# Contact_V1_0.net
KiCad netlist of a schematic drawn in EAGLE
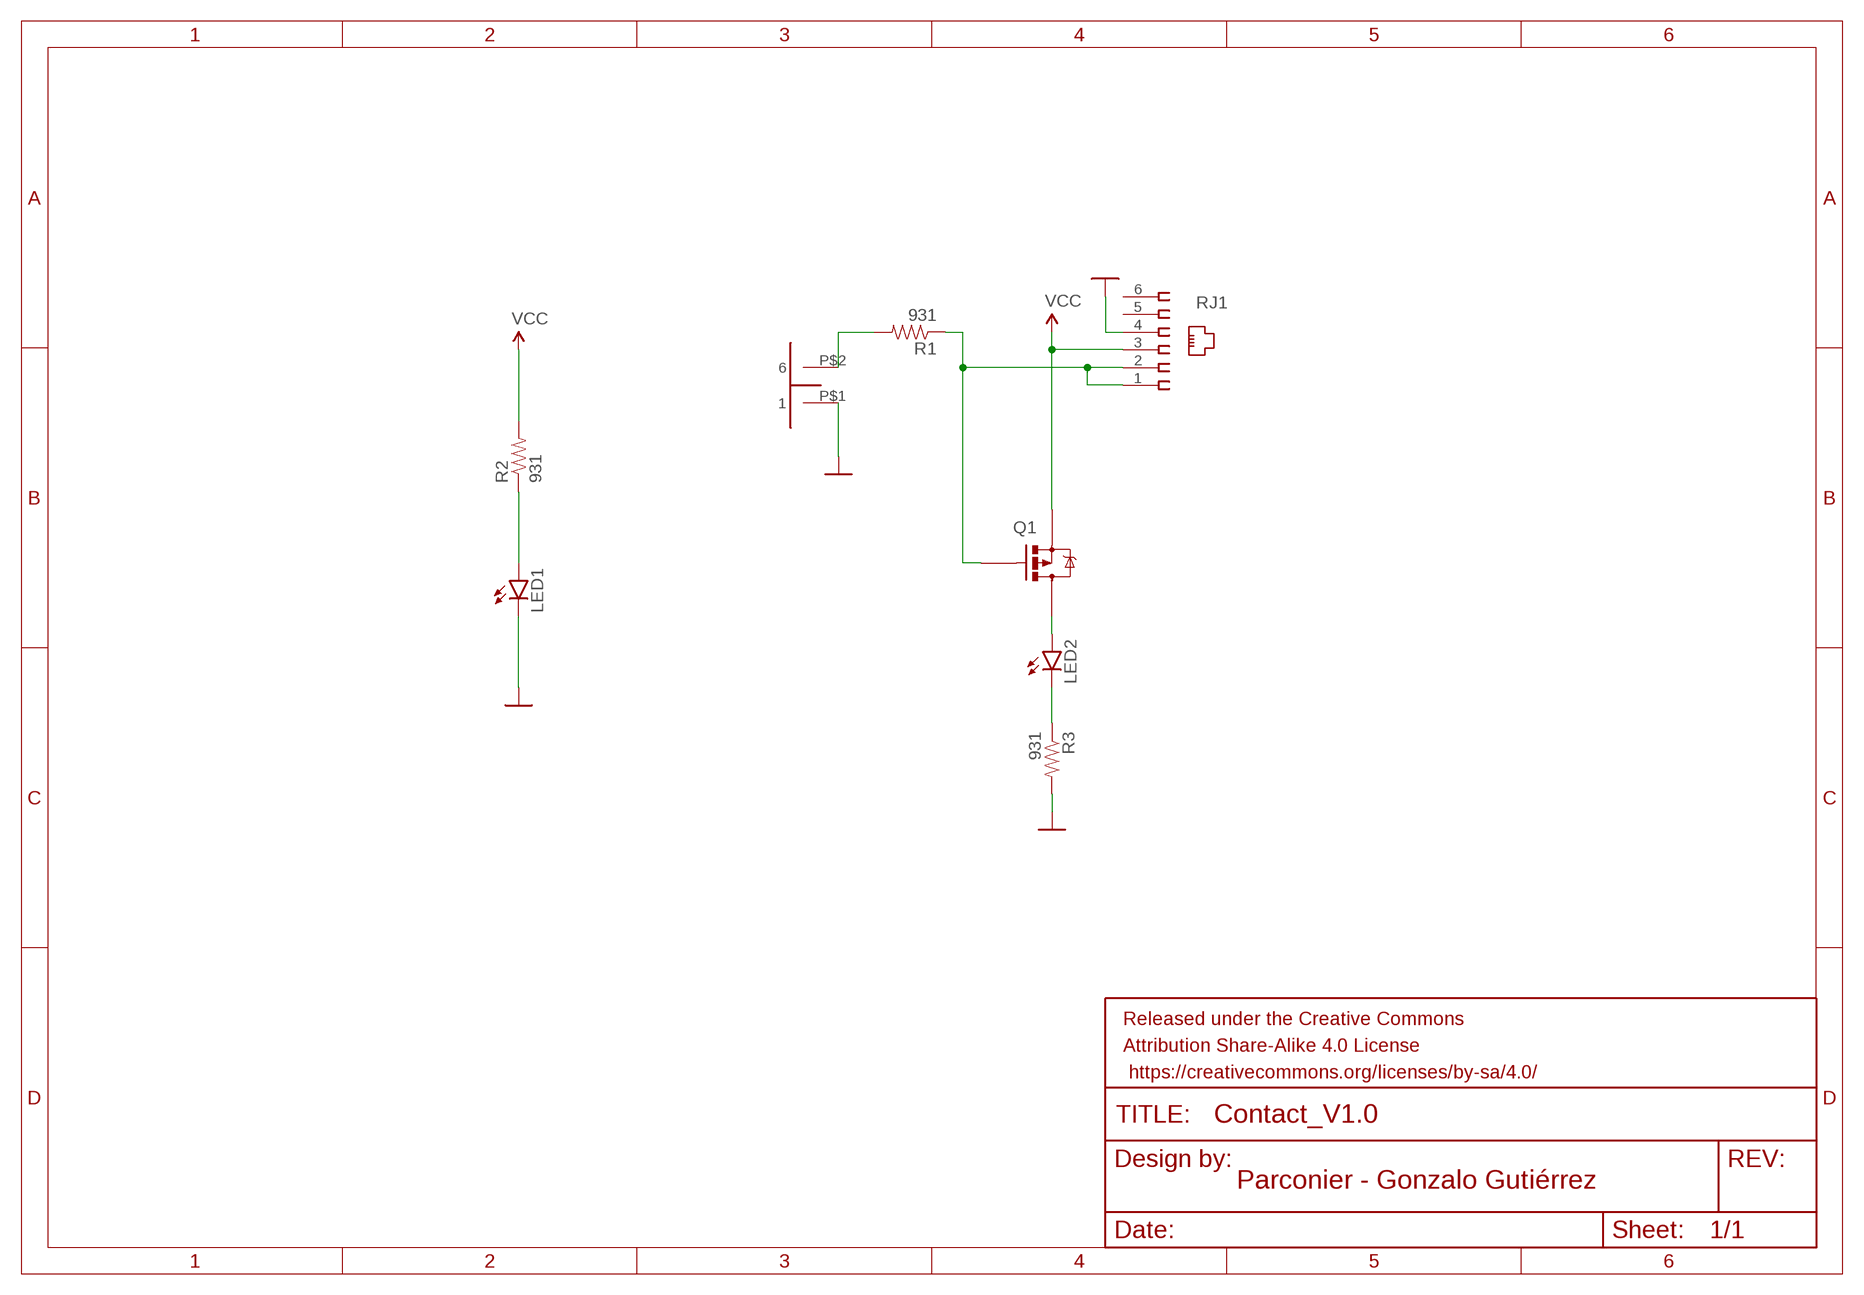
[diagram p0: schematic, sheet 1]

(export (version "E")
  (design (tool "Eeschema 10.0.6"))
  (components
    (comp (ref "LED1")
      (value "LED0603")
      (footprint "eagle-import:LED-0603")
      (fields (field (name "MPN") "LTST-C193KRKT-5A"))
      (libsource (lib "eagle-import") (part "LED0603"))
    )
    (comp (ref "LED2")
      (value "LED0603")
      (footprint "eagle-import:LED-0603")
      (fields (field (name "MPN") "LB Q39E-L2OO-35-1"))
      (libsource (lib "eagle-import") (part "LED0603"))
    )
    (comp (ref "PB1")
      (value "PUSHBUTTON_MOKO")
      (footprint "eagle-import:SUBSTITUTE_FSM104_RIGHT_ANGLE")
      (libsource (lib "eagle-import") (part "PUSHBUTTON_MOKO"))
    )
    (comp (ref "Q1")
      (value "RU1C002ZPTCL")
      (footprint "eagle-import:SOTFL65P210X105-3N")
      (libsource (lib "eagle-import") (part "RU1C002ZPTCL"))
    )
    (comp (ref "R1")
      (value "931")
      (footprint "eagle-import:RESC1005X35")
      (fields (field (name "MPN") "RC0402FR-07931RL"))
      (libsource (lib "eagle-import") (part "RES_0402"))
    )
    (comp (ref "R2")
      (value "931")
      (footprint "eagle-import:RESC1005X35")
      (fields (field (name "MPN") "RC0402FR-07931RL"))
      (libsource (lib "eagle-import") (part "RES_0402"))
    )
    (comp (ref "R3")
      (value "931")
      (footprint "eagle-import:RESC1005X35")
      (fields (field (name "MPN") "RC0402FR-07931RL"))
      (libsource (lib "eagle-import") (part "RES_0402"))
    )
    (comp (ref "RJ1")
      (value "615006138421")
      (footprint "eagle-import:615006138421")
      (fields (field (name "RS_PART_NUMBER") "7350282"))
      (libsource (lib "eagle-import") (part "615006138421"))
    )
  )
  (nets
    (net (code "1") (name "GND") (class "Default")
      (node (ref "LED1") (pin "C") (pinfunction "C_C") (pintype "passive"))
      (node (ref "PB1") (pin "P$1") (pinfunction "1_P$1") (pintype "bidirectional"))
      (node (ref "R3") (pin "2") (pinfunction "2_2") (pintype "passive"))
      (node (ref "RJ1") (pin "4") (pinfunction "4_4") (pintype "input"))
    )
    (net (code "2") (name "Net-(LED1-PadA)") (class "Default")
      (node (ref "LED1") (pin "A") (pinfunction "A_A") (pintype "passive"))
      (node (ref "R2") (pin "1") (pinfunction "1_1") (pintype "passive"))
    )
    (net (code "3") (name "Net-(LED2-PadC)") (class "Default")
      (node (ref "LED2") (pin "C") (pinfunction "C_C") (pintype "passive"))
      (node (ref "R3") (pin "1") (pinfunction "1_1") (pintype "passive"))
    )
    (net (code "4") (name "Net-(PB1-6)") (class "Default")
      (node (ref "PB1") (pin "P$2") (pinfunction "6_P$2") (pintype "bidirectional"))
      (node (ref "R1") (pin "2") (pinfunction "2_2") (pintype "passive"))
    )
    (net (code "5") (name "Net-(Q1-D)") (class "Default")
      (node (ref "LED2") (pin "A") (pinfunction "A_A") (pintype "passive"))
      (node (ref "Q1") (pin "3") (pinfunction "D_3") (pintype "bidirectional"))
    )
    (net (code "6") (name "Net-(Q1-G)") (class "Default")
      (node (ref "Q1") (pin "1") (pinfunction "G_1") (pintype "bidirectional"))
      (node (ref "R1") (pin "1") (pinfunction "1_1") (pintype "passive"))
      (node (ref "RJ1") (pin "1") (pinfunction "1_1") (pintype "input"))
      (node (ref "RJ1") (pin "2") (pinfunction "2_2") (pintype "input"))
    )
    (net (code "7") (name "VCC") (class "Default")
      (node (ref "Q1") (pin "2") (pinfunction "S_2") (pintype "bidirectional"))
      (node (ref "R2") (pin "2") (pinfunction "2_2") (pintype "passive"))
      (node (ref "RJ1") (pin "3") (pinfunction "3_3") (pintype "input"))
    )
    (net (code "8") (name "unconnected-(RJ1-Pad5)") (class "Default")
      (node (ref "RJ1") (pin "5") (pinfunction "5_5") (pintype "input"))
    )
    (net (code "9") (name "unconnected-(RJ1-Pad6)") (class "Default")
      (node (ref "RJ1") (pin "6") (pinfunction "6_6") (pintype "input"))
    )
  )
)
